# USB.net
KiCad netlist of a schematic drawn in Altium Designer
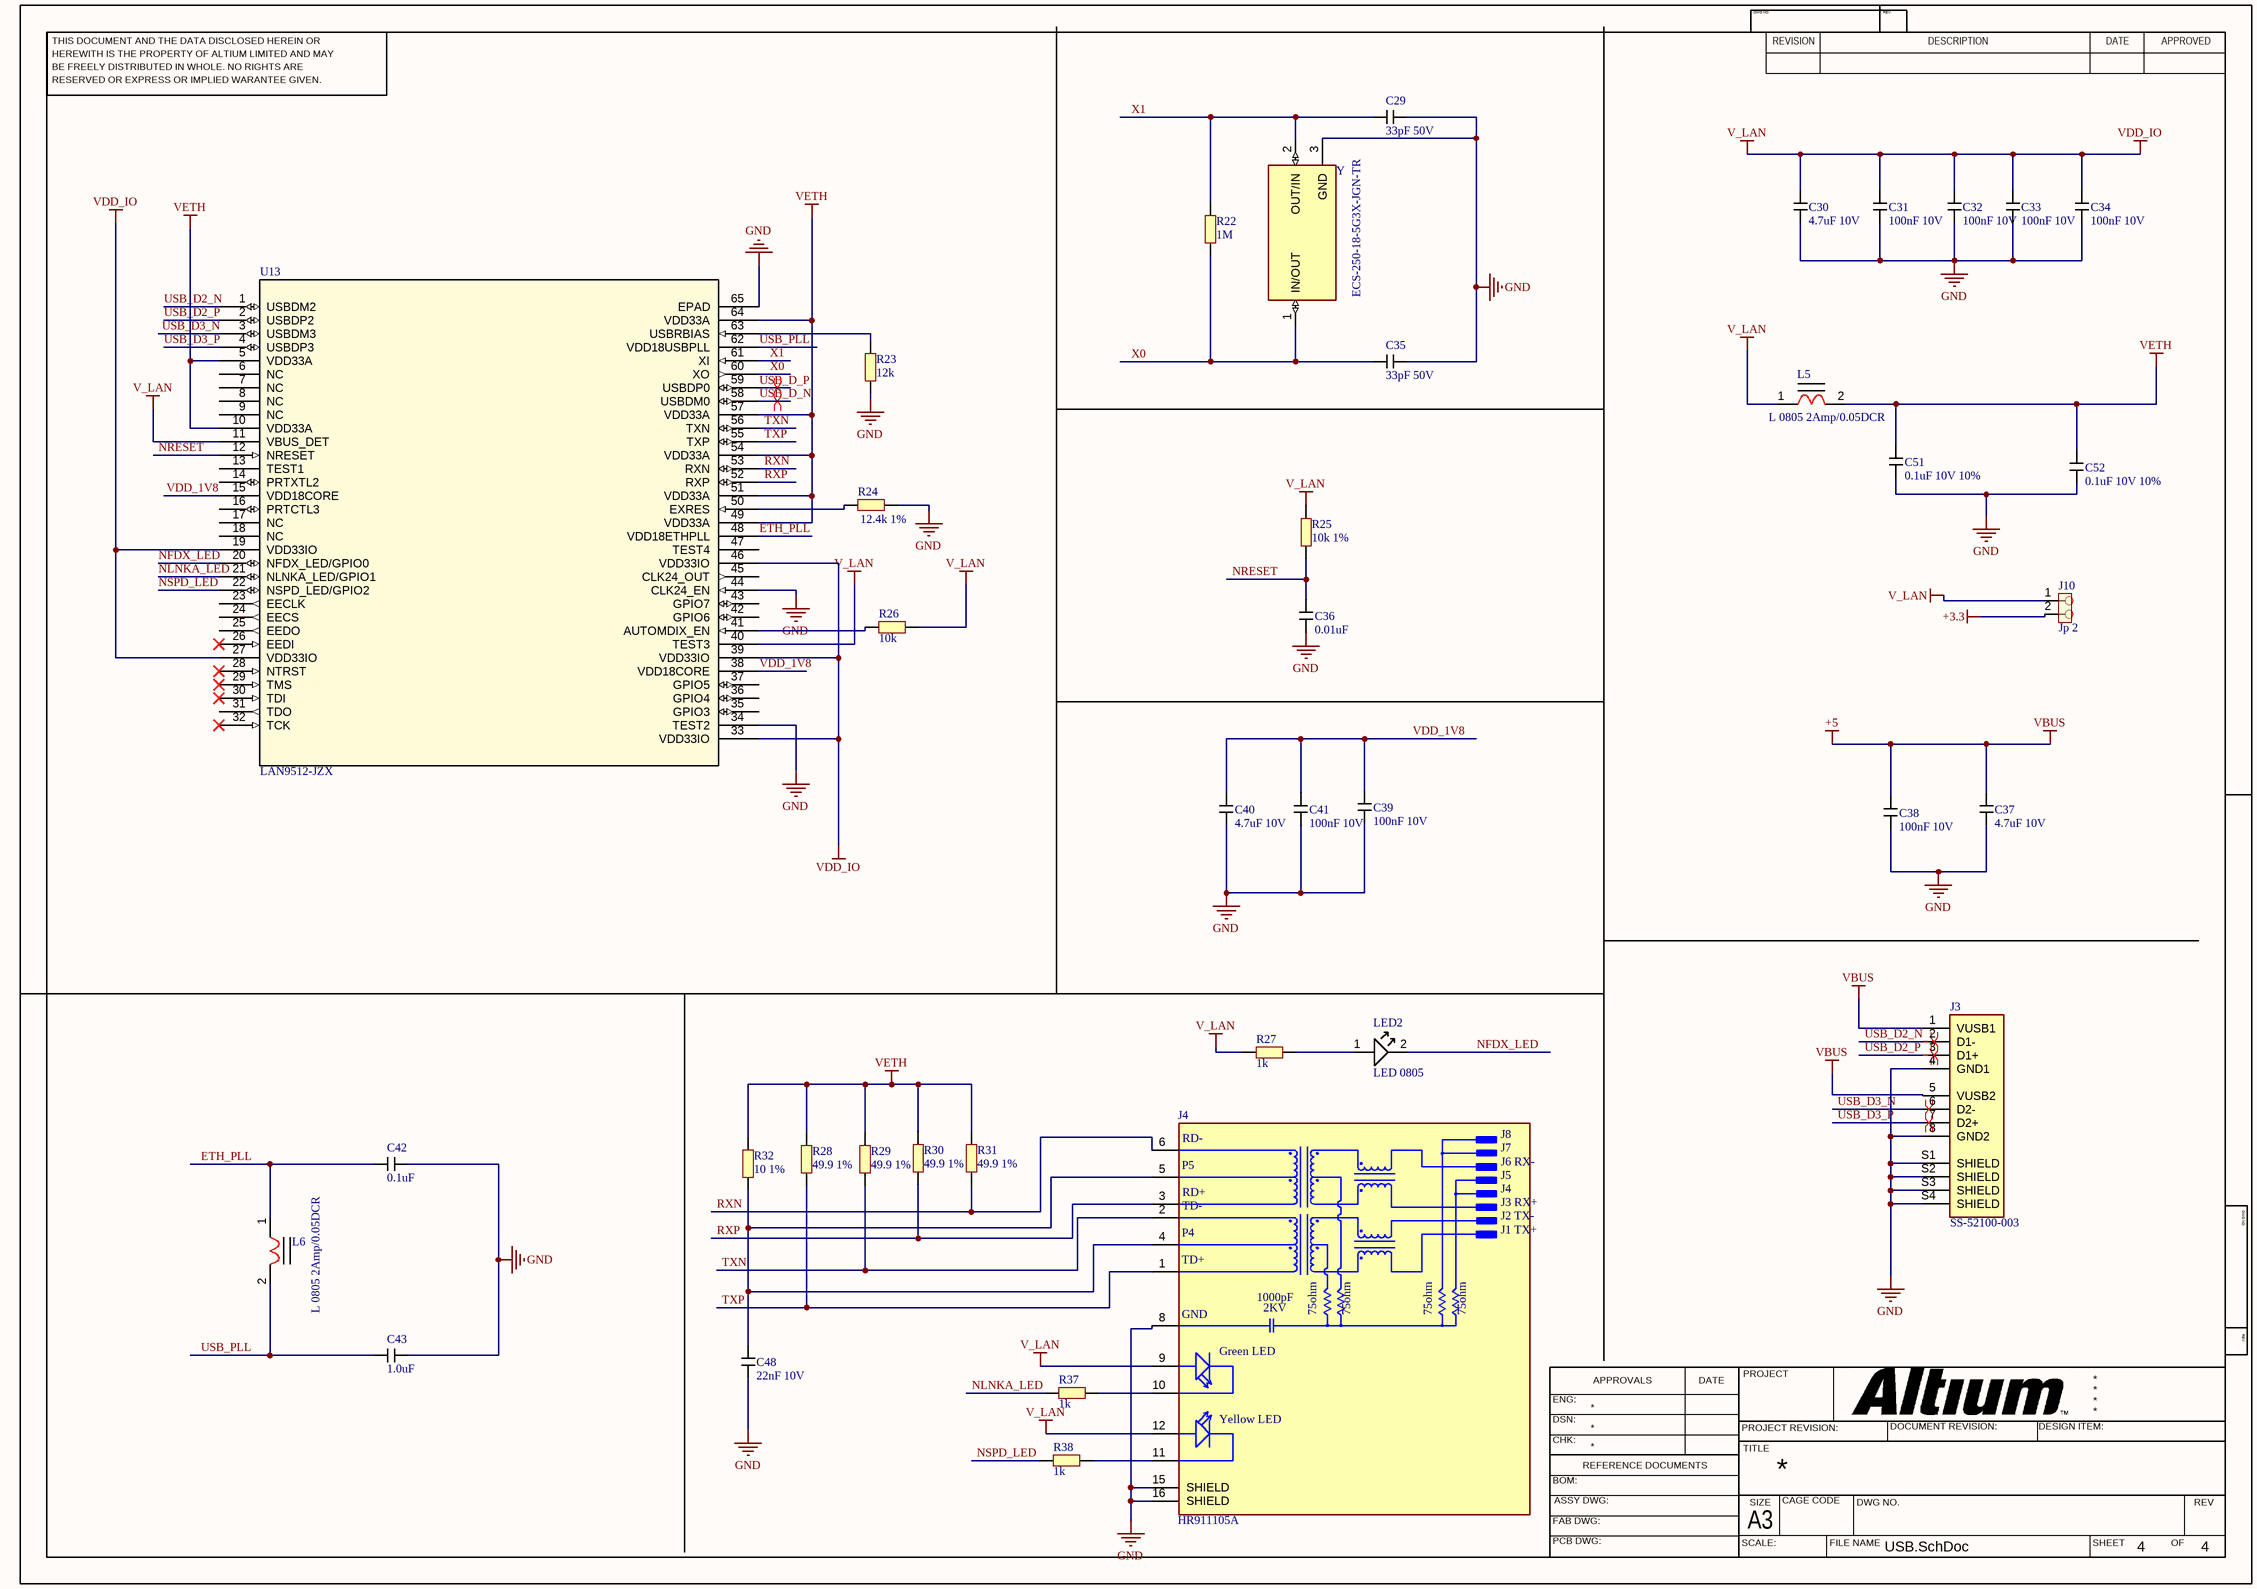
[diagram p0: USB.SchDoc]

(export (version "E")
  (design (tool "Eeschema 10.0.6"))
  (components
    (comp (ref "C29") (value "33pF 50V") (footprint "c 0805") (libsource (lib "NAVISTAR") (part "C 0805")))
    (comp (ref "C30") (value "4.7uF 10V") (footprint "c 0805") (libsource (lib "NAVISTAR") (part "C 0805")))
    (comp (ref "C31") (value "100nF 10V") (footprint "c 0805") (libsource (lib "NAVISTAR") (part "C 0805")))
    (comp (ref "C32") (value "100nF 10V") (footprint "c 0805") (libsource (lib "NAVISTAR") (part "C 0805")))
    (comp (ref "C33") (value "100nF 10V") (footprint "c 0805") (libsource (lib "NAVISTAR") (part "C 0805")))
    (comp (ref "C34") (value "100nF 10V") (footprint "c 0805") (libsource (lib "NAVISTAR") (part "C 0805")))
    (comp (ref "C35") (value "33pF 50V") (footprint "c 0805") (libsource (lib "NAVISTAR") (part "C 0805")))
    (comp (ref "C36") (value "0.01uF") (footprint "c 0805") (libsource (lib "NAVISTAR") (part "C 0805")))
    (comp (ref "C37") (value "4.7uF 10V") (footprint "c 0805") (libsource (lib "NAVISTAR") (part "C 0805")))
    (comp (ref "C38") (value "100nF 10V") (footprint "c 0805") (libsource (lib "NAVISTAR") (part "C 0805")))
    (comp (ref "C39") (value "100nF 10V") (footprint "c 0805") (libsource (lib "NAVISTAR") (part "C 0805")))
    (comp (ref "C40") (value "4.7uF 10V") (footprint "c 0805") (libsource (lib "NAVISTAR") (part "C 0805")))
    (comp (ref "C41") (value "100nF 10V") (footprint "c 0805") (libsource (lib "NAVISTAR") (part "C 0805")))
    (comp (ref "C42") (value "0.1uF") (footprint "c 0805") (libsource (lib "NAVISTAR") (part "C 0805")))
    (comp (ref "C43") (value "1.0uF") (footprint "c 0805") (libsource (lib "NAVISTAR") (part "C 0805")))
    (comp (ref "C48") (value "22nF 10V") (footprint "c 0805") (libsource (lib "Lab1") (part "C 0805")))
    (comp (ref "C51")
      (value "0.1uF 10V 10%")
      (footprint "c 0805")
      (libsource (lib "NAVISTAR") (part "C 0805"))
    )
    (comp (ref "C52")
      (value "0.1uF 10V 10%")
      (footprint "c 0805")
      (libsource (lib "NAVISTAR") (part "C 0805"))
    )
    (comp (ref "J3")
      (value "SS-52100-003")
      (footprint "BEL_SS-52100-003")
      (description "USB 2.0 - A Connector ¦ 2 Port ¦ Stacked Right Angle Receptacle ¦ Shielded")
      (fields (field (name "DIGI-KEY_PART_NUMBER") "380-1414-ND") (field (name "MF") "Stewart Connector"))
      (libsource (lib "SS-52100-003") (part "SS-52100-003"))
    )
    (comp (ref "J4")
      (value "HR911105A")
      (footprint "HANRUN_HR911105A")
      (description "DIP RJ45 Connector;")
      (fields (field (name "MF") "hanrun"))
      (libsource (lib "HR911105A") (part "HR911105A"))
    )
    (comp (ref "J10") (value "Jp 2") (footprint "Jp2") (libsource (lib "NAVISTAR") (part "Jp 2")))
    (comp (ref "L5")
      (value "L 0805 2Amp/0.05DCR")
      (footprint "Ferrite 0805")
      (libsource (lib "NAVISTAR") (part "Ferite 0805"))
    )
    (comp (ref "L6")
      (value "L 0805 2Amp/0.05DCR")
      (footprint "Ferrite 0805")
      (libsource (lib "NAVISTAR") (part "Ferite 0805"))
    )
    (comp (ref "LED2")
      (value "LED 0805")
      (footprint "LED 0805")
      (libsource (lib "NAVISTAR") (part "LED 0805"))
    )
    (comp (ref "R22") (value "1M") (footprint "R 0805") (libsource (lib "") (part "R 0805_1")))
    (comp (ref "R23") (value "12k") (footprint "R 0805") (libsource (lib "") (part "R 0805_1")))
    (comp (ref "R24") (value "12.4k 1%") (footprint "R 0805") (libsource (lib "NAVISTAR") (part "R 0805")))
    (comp (ref "R25") (value "10k 1%") (footprint "R 0805") (libsource (lib "") (part "R 0805_1")))
    (comp (ref "R26") (value "10k") (footprint "R 0805") (libsource (lib "NAVISTAR") (part "R 0805")))
    (comp (ref "R27") (value "1k") (footprint "R 0805") (libsource (lib "NAVISTAR") (part "R 0805")))
    (comp (ref "R28") (value "49.9 1%") (footprint "R 0805") (libsource (lib "") (part "R 0805_1")))
    (comp (ref "R29") (value "49.9 1%") (footprint "R 0805") (libsource (lib "") (part "R 0805_1")))
    (comp (ref "R30") (value "49.9 1%") (footprint "R 0805") (libsource (lib "") (part "R 0805_1")))
    (comp (ref "R31") (value "49.9 1%") (footprint "R 0805") (libsource (lib "") (part "R 0805_1")))
    (comp (ref "R32") (value "10 1%") (footprint "R 0805") (libsource (lib "") (part "R 0805_1")))
    (comp (ref "R37") (value "1k") (footprint "R 0805") (libsource (lib "NAVISTAR") (part "R 0805")))
    (comp (ref "R38") (value "1k") (footprint "R 0805") (libsource (lib "NAVISTAR") (part "R 0805")))
    (comp (ref "U13")
      (value "LAN9512-JZX")
      (footprint "QFN50P900X900X100-65N-D")
      (description "No Description Available")
      (fields
        (field (name "MANUFACTURER_PART_NUMBER") "LAN9512-JZX-TR")
        (field (name "COPYRIGHT") "Copyright (C) 2023 Ultra Librarian. All rights reserved.")
      )
      (libsource (lib "LAN9512-JZX-TR") (part "LAN9512-JZX-TR"))
    )
    (comp (ref "Y")
      (value "ECS-250-18-5G3X-JGN-TR")
      (footprint "XTAL_ECS-250-18-5G3X-JGN-TR")
      (description "25MHz Â±20ppm Crystal 18pF 30 Ohms HC-49/US")
      (fields (field (name "MF") "ECS Inc."))
      (libsource (lib "ECS-250-18-5G3X-JGN-TR") (part "ECS-250-18-5G3X-JGN-TR"))
    )
  )
  (nets
    (net (code "1") (name "+3.3") (class "Default") (node (ref "J10") (pin "2") (pintype "passive")))
    (net (code "2") (name "+5") (class "Default")
      (node (ref "C37") (pin "2") (pintype "passive"))
      (node (ref "C38") (pin "1") (pintype "passive"))
      (node (ref "J3") (pin "1") (pinfunction "VUSB1_1") (pintype "passive"))
      (node (ref "J3") (pin "5") (pinfunction "VUSB2_5") (pintype "passive"))
    )
    (net (code "3") (name "/ETH_PLL") (class "Default")
      (node (ref "C42") (pin "1") (pintype "passive"))
      (node (ref "L6") (pin "1") (pintype "passive"))
      (node (ref "U13") (pin "48") (pinfunction "VDD18ETHPLL_48") (pintype "power_in"))
    )
    (net (code "4") (name "/NFDX_LED") (class "Default")
      (node (ref "LED2") (pin "2") (pintype "passive"))
      (node (ref "U13") (pin "20") (pinfunction "NFDX_LED/GPIO0_20") (pintype "bidirectional"))
    )
    (net (code "5") (name "/NLNKA_LED") (class "Default")
      (node (ref "R37") (pin "1") (pintype "passive"))
      (node (ref "U13") (pin "21") (pinfunction "NLNKA_LED/GPIO1_21") (pintype "bidirectional"))
    )
    (net (code "6") (name "/NRESET") (class "Default")
      (node (ref "C36") (pin "2") (pintype "passive"))
      (node (ref "R25") (pin "1") (pintype "passive"))
      (node (ref "U13") (pin "12") (pinfunction "NRESET_12") (pintype "input"))
    )
    (net (code "7") (name "/NSPD_LED") (class "Default")
      (node (ref "R38") (pin "1") (pintype "passive"))
      (node (ref "U13") (pin "22") (pinfunction "NSPD_LED/GPIO2_22") (pintype "bidirectional"))
    )
    (net (code "8") (name "/RXN") (class "Default")
      (node (ref "J4") (pin "6") (pinfunction "RD-_6") (pintype "passive"))
      (node (ref "R31") (pin "1") (pintype "passive"))
      (node (ref "U13") (pin "53") (pinfunction "RXN_53") (pintype "bidirectional"))
    )
    (net (code "9") (name "/RXP") (class "Default")
      (node (ref "J4") (pin "3") (pinfunction "RD+_3") (pintype "passive"))
      (node (ref "R30") (pin "1") (pintype "passive"))
      (node (ref "U13") (pin "52") (pinfunction "RXP_52") (pintype "bidirectional"))
    )
    (net (code "10") (name "/TXN") (class "Default")
      (node (ref "J4") (pin "2") (pinfunction "TD-_2") (pintype "passive"))
      (node (ref "R29") (pin "1") (pintype "passive"))
      (node (ref "U13") (pin "56") (pinfunction "TXN_56") (pintype "bidirectional"))
    )
    (net (code "11") (name "/TXP") (class "Default")
      (node (ref "J4") (pin "1") (pinfunction "TD+_1") (pintype "passive"))
      (node (ref "R28") (pin "1") (pintype "passive"))
      (node (ref "U13") (pin "55") (pinfunction "TXP_55") (pintype "bidirectional"))
    )
    (net (code "12") (name "/USB_D2_N") (class "Default")
      (node (ref "J3") (pin "2") (pinfunction "D1-_2") (pintype "passive"))
      (node (ref "U13") (pin "1") (pinfunction "USBDM2_1") (pintype "bidirectional"))
    )
    (net (code "13") (name "/USB_D2_P") (class "Default")
      (node (ref "J3") (pin "3") (pinfunction "D1+_3") (pintype "passive"))
      (node (ref "U13") (pin "2") (pinfunction "USBDP2_2") (pintype "bidirectional"))
    )
    (net (code "14") (name "/USB_D3_N") (class "Default")
      (node (ref "J3") (pin "6") (pinfunction "D2-_6") (pintype "passive"))
      (node (ref "U13") (pin "3") (pinfunction "USBDM3_3") (pintype "bidirectional"))
    )
    (net (code "15") (name "/USB_D3_P") (class "Default")
      (node (ref "J3") (pin "7") (pinfunction "D2+_7") (pintype "passive"))
      (node (ref "U13") (pin "4") (pinfunction "USBDP3_4") (pintype "bidirectional"))
    )
    (net (code "16") (name "/USB_D_N") (class "Default")
      (node (ref "U13") (pin "58") (pinfunction "USBDM0_58") (pintype "bidirectional"))
    )
    (net (code "17") (name "/USB_D_P") (class "Default")
      (node (ref "U13") (pin "59") (pinfunction "USBDP0_59") (pintype "bidirectional"))
    )
    (net (code "18") (name "/USB_PLL") (class "Default")
      (node (ref "C43") (pin "2") (pintype "passive"))
      (node (ref "L6") (pin "2") (pintype "passive"))
      (node (ref "U13") (pin "62") (pinfunction "VDD18USBPLL_62") (pintype "power_in"))
    )
    (net (code "19") (name "/VDD_1V8") (class "Default")
      (node (ref "C39") (pin "2") (pintype "passive"))
      (node (ref "C40") (pin "2") (pintype "passive"))
      (node (ref "C41") (pin "2") (pintype "passive"))
      (node (ref "U13") (pin "15") (pinfunction "VDD18CORE_15") (pintype "power_in"))
      (node (ref "U13") (pin "38") (pinfunction "VDD18CORE_38") (pintype "power_in"))
    )
    (net (code "20") (name "/X0") (class "Default")
      (node (ref "C35") (pin "1") (pintype "passive"))
      (node (ref "R22") (pin "1") (pintype "passive"))
      (node (ref "U13") (pin "60") (pinfunction "XO_60") (pintype "output"))
      (node (ref "Y") (pin "1") (pinfunction "IN/OUT_1") (pintype "bidirectional"))
    )
    (net (code "21") (name "/X1") (class "Default")
      (node (ref "C29") (pin "1") (pintype "passive"))
      (node (ref "R22") (pin "2") (pintype "passive"))
      (node (ref "U13") (pin "61") (pinfunction "XI_61") (pintype "input"))
      (node (ref "Y") (pin "2") (pinfunction "OUT/IN_2") (pintype "bidirectional"))
    )
    (net (code "22") (name "GND") (class "Default")
      (node (ref "C29") (pin "2") (pintype "passive"))
      (node (ref "C30") (pin "1") (pintype "passive"))
      (node (ref "C31") (pin "1") (pintype "passive"))
      (node (ref "C32") (pin "1") (pintype "passive"))
      (node (ref "C33") (pin "1") (pintype "passive"))
      (node (ref "C34") (pin "1") (pintype "passive"))
      (node (ref "C35") (pin "2") (pintype "passive"))
      (node (ref "C36") (pin "1") (pintype "passive"))
      (node (ref "C37") (pin "1") (pintype "passive"))
      (node (ref "C38") (pin "2") (pintype "passive"))
      (node (ref "C39") (pin "1") (pintype "passive"))
      (node (ref "C40") (pin "1") (pintype "passive"))
      (node (ref "C41") (pin "1") (pintype "passive"))
      (node (ref "C42") (pin "2") (pintype "passive"))
      (node (ref "C43") (pin "1") (pintype "passive"))
      (node (ref "C48") (pin "2") (pintype "passive"))
      (node (ref "C51") (pin "1") (pintype "passive"))
      (node (ref "C52") (pin "1") (pintype "passive"))
      (node (ref "J3") (pin "4") (pinfunction "GND1_4") (pintype "passive"))
      (node (ref "J3") (pin "8") (pinfunction "GND2_8") (pintype "passive"))
      (node (ref "J3") (pin "S1") (pinfunction "SHIELD_S1") (pintype "passive"))
      (node (ref "J3") (pin "S2") (pinfunction "SHIELD_S2") (pintype "passive"))
      (node (ref "J3") (pin "S3") (pinfunction "SHIELD_S3") (pintype "passive"))
      (node (ref "J3") (pin "S4") (pinfunction "SHIELD_S4") (pintype "passive"))
      (node (ref "J4") (pin "15") (pinfunction "SHIELD_15") (pintype "passive"))
      (node (ref "J4") (pin "16") (pinfunction "SHIELD_16") (pintype "passive"))
      (node (ref "J4") (pin "8") (pinfunction "GND_8") (pintype "power_in"))
      (node (ref "R23") (pin "1") (pintype "passive"))
      (node (ref "R24") (pin "2") (pintype "passive"))
      (node (ref "U13") (pin "34") (pinfunction "TEST2_34") (pintype "passive"))
      (node (ref "U13") (pin "44") (pinfunction "CLK24_EN_44") (pintype "input"))
      (node (ref "U13") (pin "65") (pinfunction "EPAD_65") (pintype "passive"))
      (node (ref "Y") (pin "3") (pinfunction "GND_3") (pintype "power_in"))
    )
    (net (code "23") (name "Net-(J4-GC)") (class "Default")
      (node (ref "J4") (pin "10") (pinfunction "GC_10") (pintype "passive"))
      (node (ref "R37") (pin "2") (pintype "passive"))
    )
    (net (code "24") (name "Net-(J4-P4)") (class "Default")
      (node (ref "C48") (pin "1") (pintype "passive"))
      (node (ref "J4") (pin "4") (pinfunction "P4_4") (pintype "passive"))
      (node (ref "J4") (pin "5") (pinfunction "P5_5") (pintype "passive"))
      (node (ref "R32") (pin "1") (pintype "passive"))
    )
    (net (code "25") (name "Net-(J4-YC)") (class "Default")
      (node (ref "J4") (pin "11") (pinfunction "YC_11") (pintype "passive"))
      (node (ref "R38") (pin "2") (pintype "passive"))
    )
    (net (code "26") (name "Net-(LED2-Pad1)") (class "Default")
      (node (ref "LED2") (pin "1") (pintype "passive"))
      (node (ref "R27") (pin "2") (pintype "passive"))
    )
    (net (code "27") (name "Net-(U13-AUTOMDIX_EN)") (class "Default")
      (node (ref "R26") (pin "1") (pintype "passive"))
      (node (ref "U13") (pin "41") (pinfunction "AUTOMDIX_EN_41") (pintype "input"))
    )
    (net (code "28") (name "Net-(U13-EXRES)") (class "Default")
      (node (ref "R24") (pin "1") (pintype "passive"))
      (node (ref "U13") (pin "50") (pinfunction "EXRES_50") (pintype "input"))
    )
    (net (code "29") (name "Net-(U13-USBRBIAS)") (class "Default")
      (node (ref "R23") (pin "2") (pintype "passive"))
      (node (ref "U13") (pin "63") (pinfunction "USBRBIAS_63") (pintype "input"))
    )
    (net (code "30") (name "VDD_IO") (class "Default")
      (node (ref "C30") (pin "2") (pintype "passive"))
      (node (ref "C31") (pin "2") (pintype "passive"))
      (node (ref "C32") (pin "2") (pintype "passive"))
      (node (ref "C33") (pin "2") (pintype "passive"))
      (node (ref "C34") (pin "2") (pintype "passive"))
      (node (ref "J10") (pin "1") (pintype "passive"))
      (node (ref "J4") (pin "12") (pinfunction "YA_12") (pintype "passive"))
      (node (ref "J4") (pin "9") (pinfunction "GA_9") (pintype "passive"))
      (node (ref "L5") (pin "1") (pintype "passive"))
      (node (ref "R25") (pin "2") (pintype "passive"))
      (node (ref "R26") (pin "2") (pintype "passive"))
      (node (ref "R27") (pin "1") (pintype "passive"))
      (node (ref "U13") (pin "11") (pinfunction "VBUS_DET_11") (pintype "power_in"))
      (node (ref "U13") (pin "19") (pinfunction "VDD33IO_19") (pintype "power_in"))
      (node (ref "U13") (pin "27") (pinfunction "VDD33IO_27") (pintype "power_in"))
      (node (ref "U13") (pin "33") (pinfunction "VDD33IO_33") (pintype "power_in"))
      (node (ref "U13") (pin "39") (pinfunction "VDD33IO_39") (pintype "power_in"))
      (node (ref "U13") (pin "40") (pinfunction "TEST3_40") (pintype "passive"))
      (node (ref "U13") (pin "46") (pinfunction "VDD33IO_46") (pintype "power_in"))
    )
    (net (code "31") (name "VETH") (class "Default")
      (node (ref "C51") (pin "2") (pintype "passive"))
      (node (ref "C52") (pin "2") (pintype "passive"))
      (node (ref "L5") (pin "2") (pintype "passive"))
      (node (ref "R28") (pin "2") (pintype "passive"))
      (node (ref "R29") (pin "2") (pintype "passive"))
      (node (ref "R30") (pin "2") (pintype "passive"))
      (node (ref "R31") (pin "2") (pintype "passive"))
      (node (ref "R32") (pin "2") (pintype "passive"))
      (node (ref "U13") (pin "10") (pinfunction "VDD33A_10") (pintype "power_in"))
      (node (ref "U13") (pin "49") (pinfunction "VDD33A_49") (pintype "power_in"))
      (node (ref "U13") (pin "5") (pinfunction "VDD33A_5") (pintype "power_in"))
      (node (ref "U13") (pin "51") (pinfunction "VDD33A_51") (pintype "power_in"))
      (node (ref "U13") (pin "54") (pinfunction "VDD33A_54") (pintype "power_in"))
      (node (ref "U13") (pin "57") (pinfunction "VDD33A_57") (pintype "power_in"))
      (node (ref "U13") (pin "64") (pinfunction "VDD33A_64") (pintype "power_in"))
    )
    (net (code "32") (name "unconnected-(U13-CLK24_OUT-Pad45)") (class "Default")
      (node (ref "U13") (pin "45") (pinfunction "CLK24_OUT_45") (pintype "output"))
    )
    (net (code "33") (name "unconnected-(U13-EECLK-Pad23)") (class "Default")
      (node (ref "U13") (pin "23") (pinfunction "EECLK_23") (pintype "output"))
    )
    (net (code "34") (name "unconnected-(U13-EECS-Pad24)") (class "Default")
      (node (ref "U13") (pin "24") (pinfunction "EECS_24") (pintype "output"))
    )
    (net (code "35") (name "unconnected-(U13-EEDI-Pad26)") (class "Default")
      (node (ref "U13") (pin "26") (pinfunction "EEDI_26") (pintype "input+no_connect"))
    )
    (net (code "36") (name "unconnected-(U13-EEDO-Pad25)") (class "Default")
      (node (ref "U13") (pin "25") (pinfunction "EEDO_25") (pintype "output"))
    )
    (net (code "37") (name "unconnected-(U13-GPIO3-Pad35)") (class "Default")
      (node (ref "U13") (pin "35") (pinfunction "GPIO3_35") (pintype "bidirectional"))
    )
    (net (code "38") (name "unconnected-(U13-GPIO4-Pad36)") (class "Default")
      (node (ref "U13") (pin "36") (pinfunction "GPIO4_36") (pintype "bidirectional"))
    )
    (net (code "39") (name "unconnected-(U13-GPIO5-Pad37)") (class "Default")
      (node (ref "U13") (pin "37") (pinfunction "GPIO5_37") (pintype "bidirectional"))
    )
    (net (code "40") (name "unconnected-(U13-GPIO6-Pad42)") (class "Default")
      (node (ref "U13") (pin "42") (pinfunction "GPIO6_42") (pintype "bidirectional"))
    )
    (net (code "41") (name "unconnected-(U13-GPIO7-Pad43)") (class "Default")
      (node (ref "U13") (pin "43") (pinfunction "GPIO7_43") (pintype "bidirectional"))
    )
    (net (code "42") (name "unconnected-(U13-NC-Pad6)") (class "Default")
      (node (ref "U13") (pin "6") (pinfunction "NC_6") (pintype "passive"))
    )
    (net (code "43") (name "unconnected-(U13-NC-Pad7)") (class "Default")
      (node (ref "U13") (pin "7") (pinfunction "NC_7") (pintype "passive"))
    )
    (net (code "44") (name "unconnected-(U13-NC-Pad8)") (class "Default")
      (node (ref "U13") (pin "8") (pinfunction "NC_8") (pintype "passive"))
    )
    (net (code "45") (name "unconnected-(U13-NC-Pad9)") (class "Default")
      (node (ref "U13") (pin "9") (pinfunction "NC_9") (pintype "passive"))
    )
    (net (code "46") (name "unconnected-(U13-NC-Pad17)") (class "Default")
      (node (ref "U13") (pin "17") (pinfunction "NC_17") (pintype "passive"))
    )
    (net (code "47") (name "unconnected-(U13-NC-Pad18)") (class "Default")
      (node (ref "U13") (pin "18") (pinfunction "NC_18") (pintype "passive"))
    )
    (net (code "48") (name "unconnected-(U13-NTRST-Pad28)") (class "Default")
      (node (ref "U13") (pin "28") (pinfunction "NTRST_28") (pintype "input+no_connect"))
    )
    (net (code "49") (name "unconnected-(U13-PRTCTL3-Pad16)") (class "Default")
      (node (ref "U13") (pin "16") (pinfunction "PRTCTL3_16") (pintype "bidirectional"))
    )
    (net (code "50") (name "unconnected-(U13-PRTXTL2-Pad14)") (class "Default")
      (node (ref "U13") (pin "14") (pinfunction "PRTXTL2_14") (pintype "bidirectional"))
    )
    (net (code "51") (name "unconnected-(U13-TCK-Pad32)") (class "Default")
      (node (ref "U13") (pin "32") (pinfunction "TCK_32") (pintype "input+no_connect"))
    )
    (net (code "52") (name "unconnected-(U13-TDI-Pad30)") (class "Default")
      (node (ref "U13") (pin "30") (pinfunction "TDI_30") (pintype "input+no_connect"))
    )
    (net (code "53") (name "unconnected-(U13-TDO-Pad31)") (class "Default")
      (node (ref "U13") (pin "31") (pinfunction "TDO_31") (pintype "output"))
    )
    (net (code "54") (name "unconnected-(U13-TEST1-Pad13)") (class "Default")
      (node (ref "U13") (pin "13") (pinfunction "TEST1_13") (pintype "passive"))
    )
    (net (code "55") (name "unconnected-(U13-TEST4-Pad47)") (class "Default")
      (node (ref "U13") (pin "47") (pinfunction "TEST4_47") (pintype "passive"))
    )
    (net (code "56") (name "unconnected-(U13-TMS-Pad29)") (class "Default")
      (node (ref "U13") (pin "29") (pinfunction "TMS_29") (pintype "input+no_connect"))
    )
  )
)
